# version_1_OK_fixed.net
KiCad netlist of a schematic drawn in EAGLE
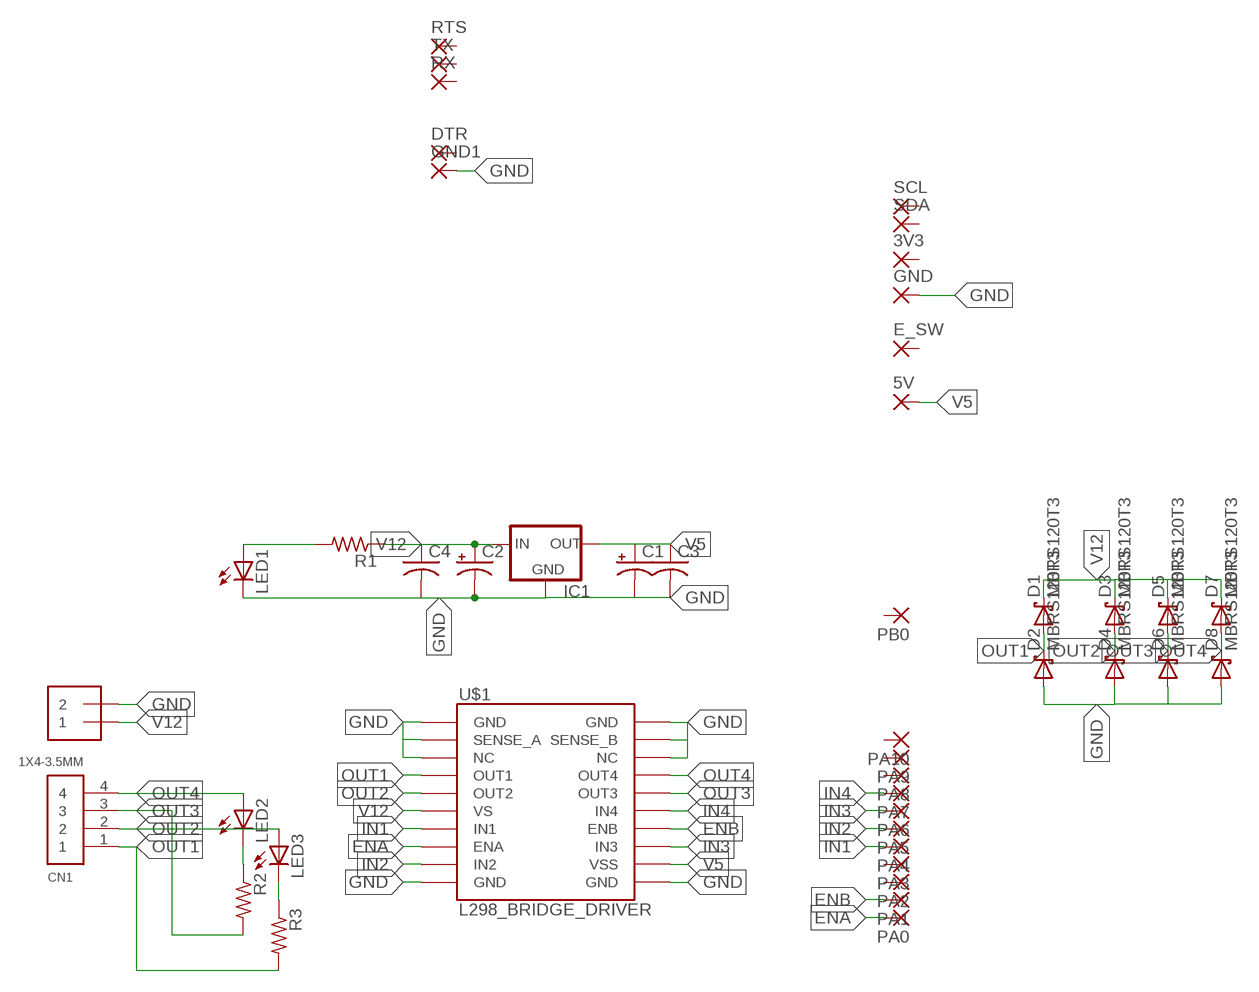
[diagram p0: schematic, sheet 1]

(export (version "E")
  (design (tool "Eeschema 10.0.6"))
  (components
    (comp (ref "3V3")
      (value "1,6/0,9")
      (footprint "eagle-import:1,6_0,9")
      (libsource (lib "eagle-import") (part "1,6/0,9"))
    )
    (comp (ref "5V")
      (value "1,6/0,9")
      (footprint "eagle-import:1,6_0,9")
      (libsource (lib "eagle-import") (part "1,6/0,9"))
    )
    (comp (ref "C1")
      (value "CPOL-USA/3216-18R")
      (footprint "eagle-import:A_3216-18R")
      (libsource (lib "eagle-import") (part "CPOL-USA/3216-18R"))
    )
    (comp (ref "C2")
      (value "CPOL-USCT7343")
      (footprint "eagle-import:CT7343")
      (libsource (lib "eagle-import") (part "CPOL-USCT7343"))
    )
    (comp (ref "C3")
      (value "C-USC0805")
      (footprint "eagle-import:C0805")
      (libsource (lib "eagle-import") (part "C-USC0805"))
    )
    (comp (ref "C4")
      (value "C-USC0805")
      (footprint "eagle-import:C0805")
      (libsource (lib "eagle-import") (part "C-USC0805"))
    )
    (comp (ref "CN1")
      (value "1X4-3.5MM")
      (footprint "eagle-import:1X04-3.5MM")
      (libsource (lib "eagle-import") (part "1X4-3.5MM"))
    )
    (comp (ref "D1")
      (value "MBRS120T3")
      (footprint "eagle-import:DO214AA")
      (libsource (lib "eagle-import") (part "MBRS120T3"))
    )
    (comp (ref "D2")
      (value "MBRS120T3")
      (footprint "eagle-import:DO214AA")
      (libsource (lib "eagle-import") (part "MBRS120T3"))
    )
    (comp (ref "D3")
      (value "MBRS120T3")
      (footprint "eagle-import:DO214AA")
      (libsource (lib "eagle-import") (part "MBRS120T3"))
    )
    (comp (ref "D4")
      (value "MBRS120T3")
      (footprint "eagle-import:DO214AA")
      (libsource (lib "eagle-import") (part "MBRS120T3"))
    )
    (comp (ref "D5")
      (value "MBRS120T3")
      (footprint "eagle-import:DO214AA")
      (libsource (lib "eagle-import") (part "MBRS120T3"))
    )
    (comp (ref "D6")
      (value "MBRS120T3")
      (footprint "eagle-import:DO214AA")
      (libsource (lib "eagle-import") (part "MBRS120T3"))
    )
    (comp (ref "D7")
      (value "MBRS120T3")
      (footprint "eagle-import:DO214AA")
      (libsource (lib "eagle-import") (part "MBRS120T3"))
    )
    (comp (ref "D8")
      (value "MBRS120T3")
      (footprint "eagle-import:DO214AA")
      (libsource (lib "eagle-import") (part "MBRS120T3"))
    )
    (comp (ref "DTR")
      (value "1,6/0,9")
      (footprint "eagle-import:1,6_0,9")
      (libsource (lib "eagle-import") (part "1,6/0,9"))
    )
    (comp (ref "E_SW")
      (value "1,6/0,9")
      (footprint "eagle-import:1,6_0,9")
      (libsource (lib "eagle-import") (part "1,6/0,9"))
    )
    (comp (ref "GND")
      (value "1,6/0,8")
      (footprint "eagle-import:1,6_0,8")
      (libsource (lib "eagle-import") (part "1,6/0,8"))
    )
    (comp (ref "GND1")
      (value "1,6/0,9")
      (footprint "eagle-import:1,6_0,9")
      (libsource (lib "eagle-import") (part "1,6/0,9"))
    )
    (comp (ref "IC1")
      (value "LM1117")
      (footprint "eagle-import:SOT223")
      (libsource (lib "eagle-import") (part "LM1117"))
    )
    (comp (ref "J1")
      (value "1X2-3.5MM")
      (footprint "eagle-import:1X2-3.5MM")
      (libsource (lib "eagle-import") (part "1X2-3.5MM"))
    )
    (comp (ref "LED1")
      (value "LEDSMT1206")
      (footprint "eagle-import:1206")
      (libsource (lib "eagle-import") (part "LEDSMT1206"))
    )
    (comp (ref "LED2")
      (value "LEDSMT1206")
      (footprint "eagle-import:1206")
      (libsource (lib "eagle-import") (part "LEDSMT1206"))
    )
    (comp (ref "LED3")
      (value "LEDSMT1206")
      (footprint "eagle-import:1206")
      (libsource (lib "eagle-import") (part "LEDSMT1206"))
    )
    (comp (ref "PA0")
      (value "1,6/0,9")
      (footprint "eagle-import:1,6_0,9")
      (libsource (lib "eagle-import") (part "1,6/0,9"))
    )
    (comp (ref "PA1")
      (value "1,6/0,9")
      (footprint "eagle-import:1,6_0,9")
      (libsource (lib "eagle-import") (part "1,6/0,9"))
    )
    (comp (ref "PA2")
      (value "1,6/0,9")
      (footprint "eagle-import:1,6_0,9")
      (libsource (lib "eagle-import") (part "1,6/0,9"))
    )
    (comp (ref "PA3")
      (value "1,6/0,9")
      (footprint "eagle-import:1,6_0,9")
      (libsource (lib "eagle-import") (part "1,6/0,9"))
    )
    (comp (ref "PA4")
      (value "1,6/0,9")
      (footprint "eagle-import:1,6_0,9")
      (libsource (lib "eagle-import") (part "1,6/0,9"))
    )
    (comp (ref "PA5")
      (value "1,6/0,9")
      (footprint "eagle-import:1,6_0,9")
      (libsource (lib "eagle-import") (part "1,6/0,9"))
    )
    (comp (ref "PA6")
      (value "1,6/0,9")
      (footprint "eagle-import:1,6_0,9")
      (libsource (lib "eagle-import") (part "1,6/0,9"))
    )
    (comp (ref "PA7")
      (value "1,6/0,9")
      (footprint "eagle-import:1,6_0,9")
      (libsource (lib "eagle-import") (part "1,6/0,9"))
    )
    (comp (ref "PA8")
      (value "1,6/0,9")
      (footprint "eagle-import:1,6_0,9")
      (libsource (lib "eagle-import") (part "1,6/0,9"))
    )
    (comp (ref "PA9")
      (value "1,6/0,9")
      (footprint "eagle-import:1,6_0,9")
      (libsource (lib "eagle-import") (part "1,6/0,9"))
    )
    (comp (ref "PA10")
      (value "1,6/0,9")
      (footprint "eagle-import:1,6_0,9")
      (libsource (lib "eagle-import") (part "1,6/0,9"))
    )
    (comp (ref "PB0")
      (value "1,6/0,9")
      (footprint "eagle-import:1,6_0,9")
      (libsource (lib "eagle-import") (part "1,6/0,9"))
    )
    (comp (ref "R1")
      (value "R-US_R0805")
      (footprint "eagle-import:R0805")
      (libsource (lib "eagle-import") (part "R-US_R0805"))
    )
    (comp (ref "R2")
      (value "R-US_R0805")
      (footprint "eagle-import:R0805")
      (libsource (lib "eagle-import") (part "R-US_R0805"))
    )
    (comp (ref "R3")
      (value "R-US_R0805")
      (footprint "eagle-import:R0805")
      (libsource (lib "eagle-import") (part "R-US_R0805"))
    )
    (comp (ref "RTS")
      (value "1,6/0,9")
      (footprint "eagle-import:1,6_0,9")
      (libsource (lib "eagle-import") (part "1,6/0,9"))
    )
    (comp (ref "RX")
      (value "1,6/0,9")
      (footprint "eagle-import:1,6_0,9")
      (libsource (lib "eagle-import") (part "1,6/0,9"))
    )
    (comp (ref "SCL")
      (value "1,6/0,9")
      (footprint "eagle-import:1,6_0,9")
      (libsource (lib "eagle-import") (part "1,6/0,9"))
    )
    (comp (ref "SDA")
      (value "1,6/0,9")
      (footprint "eagle-import:1,6_0,9")
      (libsource (lib "eagle-import") (part "1,6/0,9"))
    )
    (comp (ref "TX")
      (value "1,6/0,9")
      (footprint "eagle-import:1,6_0,9")
      (libsource (lib "eagle-import") (part "1,6/0,9"))
    )
    (comp (ref "U$1")
      (value "L298_BRIDGE_DRIVER")
      (footprint "eagle-import:POWERSO20")
      (libsource (lib "eagle-import") (part "L298_BRIDGE_DRIVER"))
    )
  )
  (nets
    (net (code "1") (name "ENA") (class "Default")
      (node (ref "PA0") (pin "1") (pinfunction "P_1") (pintype "passive"))
      (node (ref "U$1") (pin "P$8") (pinfunction "ENA_P$8") (pintype "bidirectional"))
    )
    (net (code "2") (name "ENB") (class "Default")
      (node (ref "PA1") (pin "1") (pinfunction "P_1") (pintype "passive"))
      (node (ref "U$1") (pin "P$14") (pinfunction "ENB_P$14") (pintype "bidirectional"))
    )
    (net (code "3") (name "GND") (class "Default")
      (node (ref "C1") (pin "-") (pinfunction "-_-") (pintype "passive"))
      (node (ref "C2") (pin "-") (pinfunction "-_-") (pintype "passive"))
      (node (ref "C3") (pin "2") (pinfunction "2_2") (pintype "passive"))
      (node (ref "C4") (pin "2") (pinfunction "2_2") (pintype "passive"))
      (node (ref "D2") (pin "A") (pinfunction "A_A") (pintype "passive"))
      (node (ref "D4") (pin "A") (pinfunction "A_A") (pintype "passive"))
      (node (ref "D6") (pin "A") (pinfunction "A_A") (pintype "passive"))
      (node (ref "D8") (pin "A") (pinfunction "A_A") (pintype "passive"))
      (node (ref "GND") (pin "1") (pinfunction "P_1") (pintype "passive"))
      (node (ref "GND1") (pin "1") (pinfunction "P_1") (pintype "passive"))
      (node (ref "IC1") (pin "1") (pinfunction "GND_1") (pintype "input"))
      (node (ref "J1") (pin "2") (pinfunction "2_2") (pintype "passive"))
      (node (ref "LED1") (pin "C") (pinfunction "C_C") (pintype "passive"))
      (node (ref "U$1") (pin "P$1") (pinfunction "GND_P$1") (pintype "bidirectional"))
      (node (ref "U$1") (pin "P$10") (pinfunction "GND_P$10") (pintype "bidirectional"))
      (node (ref "U$1") (pin "P$11") (pinfunction "GND_P$11") (pintype "bidirectional"))
      (node (ref "U$1") (pin "P$18") (pinfunction "NC_P$18") (pintype "bidirectional"))
      (node (ref "U$1") (pin "P$19") (pinfunction "SENSE_B_P$19") (pintype "bidirectional"))
      (node (ref "U$1") (pin "P$2") (pinfunction "SENSE_A_P$2") (pintype "bidirectional"))
      (node (ref "U$1") (pin "P$20") (pinfunction "GND_P$20") (pintype "bidirectional"))
      (node (ref "U$1") (pin "P$3") (pinfunction "NC_P$3") (pintype "bidirectional"))
    )
    (net (code "4") (name "IN1") (class "Default")
      (node (ref "PA4") (pin "1") (pinfunction "P_1") (pintype "passive"))
      (node (ref "U$1") (pin "P$7") (pinfunction "IN1_P$7") (pintype "bidirectional"))
    )
    (net (code "5") (name "IN2") (class "Default")
      (node (ref "PA5") (pin "1") (pinfunction "P_1") (pintype "passive"))
      (node (ref "U$1") (pin "P$9") (pinfunction "IN2_P$9") (pintype "bidirectional"))
    )
    (net (code "6") (name "IN3") (class "Default")
      (node (ref "PA6") (pin "1") (pinfunction "P_1") (pintype "passive"))
      (node (ref "U$1") (pin "P$13") (pinfunction "IN3_P$13") (pintype "bidirectional"))
    )
    (net (code "7") (name "IN4") (class "Default")
      (node (ref "PA7") (pin "1") (pinfunction "P_1") (pintype "passive"))
      (node (ref "U$1") (pin "P$15") (pinfunction "IN4_P$15") (pintype "bidirectional"))
    )
    (net (code "8") (name "Net-(LED1-PadA)") (class "Default")
      (node (ref "LED1") (pin "A") (pinfunction "A_A") (pintype "passive"))
      (node (ref "R1") (pin "2") (pinfunction "2_2") (pintype "passive"))
    )
    (net (code "9") (name "Net-(LED2-PadC)") (class "Default")
      (node (ref "LED2") (pin "C") (pinfunction "C_C") (pintype "passive"))
      (node (ref "R2") (pin "1") (pinfunction "1_1") (pintype "passive"))
    )
    (net (code "10") (name "Net-(LED3-PadC)") (class "Default")
      (node (ref "LED3") (pin "C") (pinfunction "C_C") (pintype "passive"))
      (node (ref "R3") (pin "1") (pinfunction "1_1") (pintype "passive"))
    )
    (net (code "11") (name "OUT1") (class "Default")
      (node (ref "CN1") (pin "1") (pinfunction "1_1") (pintype "bidirectional"))
      (node (ref "D1") (pin "A") (pinfunction "A_A") (pintype "passive"))
      (node (ref "D2") (pin "C") (pinfunction "C_C") (pintype "passive"))
      (node (ref "R3") (pin "2") (pinfunction "2_2") (pintype "passive"))
      (node (ref "U$1") (pin "P$4") (pinfunction "OUT1_P$4") (pintype "bidirectional"))
    )
    (net (code "12") (name "OUT2") (class "Default")
      (node (ref "CN1") (pin "2") (pinfunction "2_2") (pintype "bidirectional"))
      (node (ref "D3") (pin "A") (pinfunction "A_A") (pintype "passive"))
      (node (ref "D4") (pin "C") (pinfunction "C_C") (pintype "passive"))
      (node (ref "LED3") (pin "A") (pinfunction "A_A") (pintype "passive"))
      (node (ref "U$1") (pin "P$5") (pinfunction "OUT2_P$5") (pintype "bidirectional"))
    )
    (net (code "13") (name "OUT3") (class "Default")
      (node (ref "CN1") (pin "3") (pinfunction "3_3") (pintype "bidirectional"))
      (node (ref "D5") (pin "A") (pinfunction "A_A") (pintype "passive"))
      (node (ref "D6") (pin "C") (pinfunction "C_C") (pintype "passive"))
      (node (ref "R2") (pin "2") (pinfunction "2_2") (pintype "passive"))
      (node (ref "U$1") (pin "P$16") (pinfunction "OUT3_P$16") (pintype "bidirectional"))
    )
    (net (code "14") (name "OUT4") (class "Default")
      (node (ref "CN1") (pin "4") (pinfunction "4_4") (pintype "bidirectional"))
      (node (ref "D7") (pin "A") (pinfunction "A_A") (pintype "passive"))
      (node (ref "D8") (pin "C") (pinfunction "C_C") (pintype "passive"))
      (node (ref "LED2") (pin "A") (pinfunction "A_A") (pintype "passive"))
      (node (ref "U$1") (pin "P$17") (pinfunction "OUT4_P$17") (pintype "bidirectional"))
    )
    (net (code "15") (name "V5") (class "Default")
      (node (ref "5V") (pin "1") (pinfunction "P_1") (pintype "passive"))
      (node (ref "C1") (pin "+") (pinfunction "+_+") (pintype "passive"))
      (node (ref "C3") (pin "1") (pinfunction "1_1") (pintype "passive"))
      (node (ref "IC1") (pin "2") (pinfunction "OUT_2") (pintype "passive"))
      (node (ref "U$1") (pin "P$12") (pinfunction "VSS_P$12") (pintype "bidirectional"))
    )
    (net (code "16") (name "V12") (class "Default")
      (node (ref "C2") (pin "+") (pinfunction "+_+") (pintype "passive"))
      (node (ref "C4") (pin "1") (pinfunction "1_1") (pintype "passive"))
      (node (ref "D1") (pin "C") (pinfunction "C_C") (pintype "passive"))
      (node (ref "D3") (pin "C") (pinfunction "C_C") (pintype "passive"))
      (node (ref "D5") (pin "C") (pinfunction "C_C") (pintype "passive"))
      (node (ref "D7") (pin "C") (pinfunction "C_C") (pintype "passive"))
      (node (ref "IC1") (pin "3") (pinfunction "IN_3") (pintype "input"))
      (node (ref "J1") (pin "1") (pinfunction "1_1") (pintype "passive"))
      (node (ref "R1") (pin "1") (pinfunction "1_1") (pintype "passive"))
      (node (ref "U$1") (pin "P$6") (pinfunction "VS_P$6") (pintype "bidirectional"))
    )
    (net (code "17") (name "unconnected-(3V3-P-Pad1)") (class "Default")
      (node (ref "3V3") (pin "1") (pinfunction "P_1") (pintype "passive"))
    )
    (net (code "18") (name "unconnected-(DTR-P-Pad1)") (class "Default")
      (node (ref "DTR") (pin "1") (pinfunction "P_1") (pintype "passive"))
    )
    (net (code "19") (name "unconnected-(E_SW-P-Pad1)") (class "Default")
      (node (ref "E_SW") (pin "1") (pinfunction "P_1") (pintype "passive"))
    )
    (net (code "20") (name "unconnected-(PA2-P-Pad1)") (class "Default")
      (node (ref "PA2") (pin "1") (pinfunction "P_1") (pintype "passive"))
    )
    (net (code "21") (name "unconnected-(PA3-P-Pad1)") (class "Default")
      (node (ref "PA3") (pin "1") (pinfunction "P_1") (pintype "passive"))
    )
    (net (code "22") (name "unconnected-(PA8-P-Pad1)") (class "Default")
      (node (ref "PA8") (pin "1") (pinfunction "P_1") (pintype "passive"))
    )
    (net (code "23") (name "unconnected-(PA9-P-Pad1)") (class "Default")
      (node (ref "PA9") (pin "1") (pinfunction "P_1") (pintype "passive"))
    )
    (net (code "24") (name "unconnected-(PA10-P-Pad1)") (class "Default")
      (node (ref "PA10") (pin "1") (pinfunction "P_1") (pintype "passive"))
    )
    (net (code "25") (name "unconnected-(PB0-P-Pad1)") (class "Default")
      (node (ref "PB0") (pin "1") (pinfunction "P_1") (pintype "passive"))
    )
    (net (code "26") (name "unconnected-(RTS-P-Pad1)") (class "Default")
      (node (ref "RTS") (pin "1") (pinfunction "P_1") (pintype "passive"))
    )
    (net (code "27") (name "unconnected-(RX-P-Pad1)") (class "Default")
      (node (ref "RX") (pin "1") (pinfunction "P_1") (pintype "passive"))
    )
    (net (code "28") (name "unconnected-(SCL-P-Pad1)") (class "Default")
      (node (ref "SCL") (pin "1") (pinfunction "P_1") (pintype "passive"))
    )
    (net (code "29") (name "unconnected-(SDA-P-Pad1)") (class "Default")
      (node (ref "SDA") (pin "1") (pinfunction "P_1") (pintype "passive"))
    )
    (net (code "30") (name "unconnected-(TX-P-Pad1)") (class "Default")
      (node (ref "TX") (pin "1") (pinfunction "P_1") (pintype "passive"))
    )
  )
)
